# Sheet_motors.net
KiCad netlist of a schematic drawn in Altium Designer
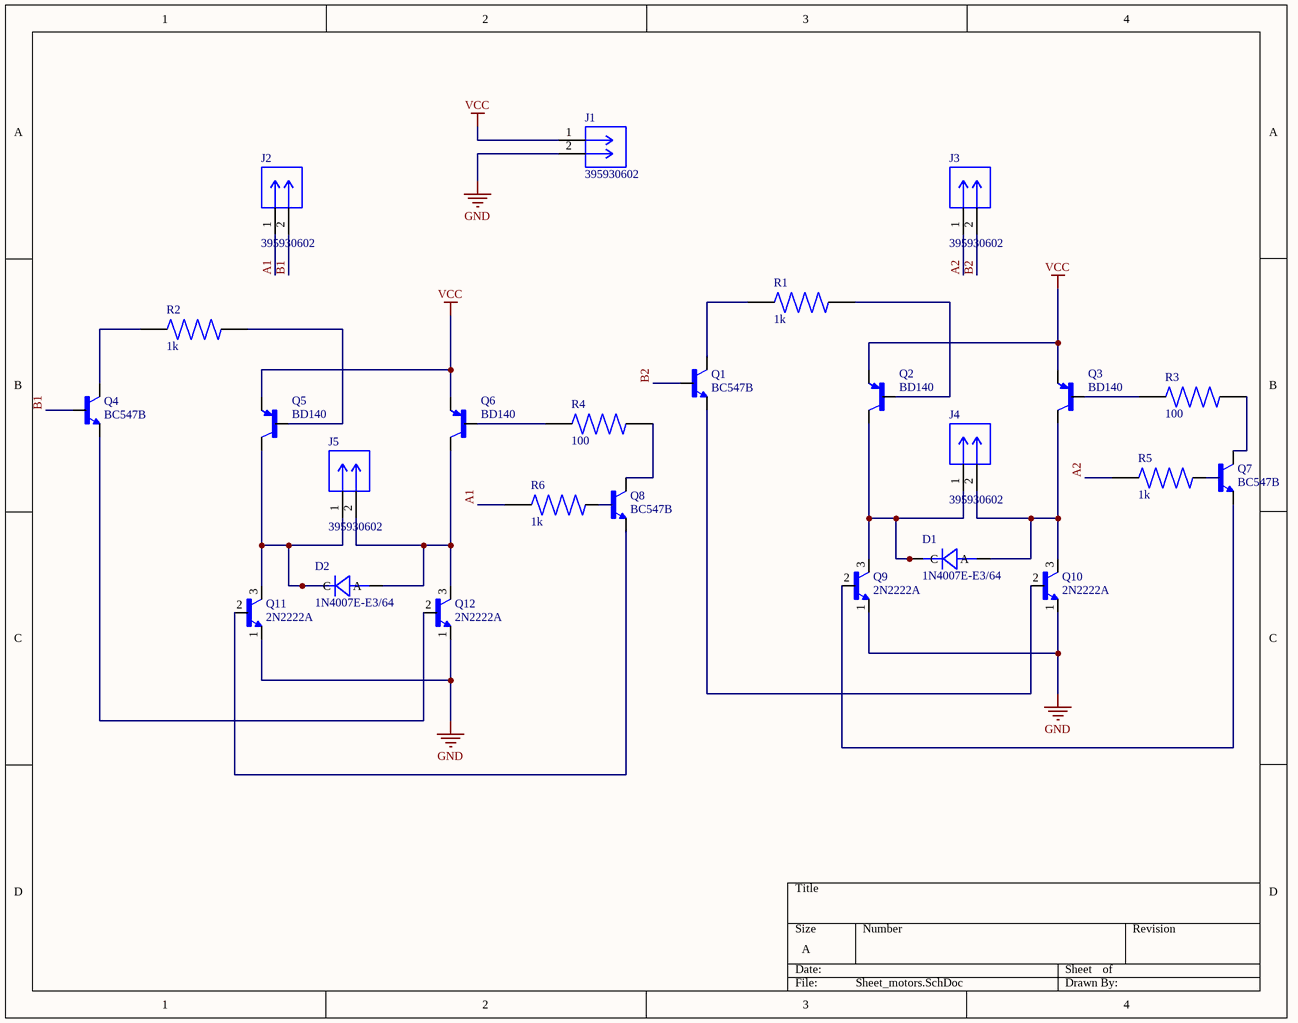
[diagram p0: Sheet_motors.SchDoc]

(export (version "E")
  (design (tool "Eeschema 10.0.6"))
  (components
    (comp (ref "D1")
      (value "1N4007E-E3/64")
      (footprint "DIOAD520W79L463D238")
      (description "Diode 1KV 1A 2-Pin DO-204AL T/R")
      (fields (field (name "MF") "Vishay Semiconductor"))
      (libsource (lib "1N4007E-E3_64") (part "1N4007E-E3/64"))
    )
    (comp (ref "D2")
      (value "1N4007E-E3/64")
      (footprint "DIOAD520W79L463D238")
      (description "Diode 1KV 1A 2-Pin DO-204AL T/R")
      (fields (field (name "MF") "Vishay Semiconductor"))
      (libsource (lib "1N4007E-E3_64") (part "1N4007E-E3/64"))
    )
    (comp (ref "J1")
      (value "395930602")
      (footprint "CONN_SD-39543-004_NONE_02P_MOL")
      (libsource (lib "395930602") (part "395930602"))
    )
    (comp (ref "J2")
      (value "395930602")
      (footprint "CONN_SD-39543-004_NONE_02P_MOL")
      (libsource (lib "395930602") (part "395930602"))
    )
    (comp (ref "J3")
      (value "395930602")
      (footprint "CONN_SD-39543-004_NONE_02P_MOL")
      (libsource (lib "395930602") (part "395930602"))
    )
    (comp (ref "J4")
      (value "395930602")
      (footprint "CONN_SD-39543-004_NONE_02P_MOL")
      (libsource (lib "395930602") (part "395930602"))
    )
    (comp (ref "J5")
      (value "395930602")
      (footprint "CONN_SD-39543-004_NONE_02P_MOL")
      (libsource (lib "395930602") (part "395930602"))
    )
    (comp (ref "Q1")
      (value "BC547B")
      (footprint "TO92250P510H770-3")
      (description "Bipolar (BJT) TransistÃ¶r NPN 45 V 100 mA 300MHz 625 mW Delikten TO-92 (TO-226)")
      (fields (field (name "MF") "ON Semiconductor"))
      (libsource (lib "BC547B") (part "BC547B"))
    )
    (comp (ref "Q2")
      (value "BD140")
      (footprint "TO229P760X270X1364-3")
      (description "Bipolar (BJT) Transistor PNP 80 V 1.5 A - 1.25 W Through Hole TO-126-3")
      (fields (field (name "MF") "ON Semiconductor"))
      (libsource (lib "BD140") (part "BD140"))
    )
    (comp (ref "Q3")
      (value "BD140")
      (footprint "TO229P760X270X1364-3")
      (description "Bipolar (BJT) Transistor PNP 80 V 1.5 A - 1.25 W Through Hole TO-126-3")
      (fields (field (name "MF") "ON Semiconductor"))
      (libsource (lib "BD140") (part "BD140"))
    )
    (comp (ref "Q4")
      (value "BC547B")
      (footprint "TO92250P510H770-3")
      (description "Bipolar (BJT) TransistÃ¶r NPN 45 V 100 mA 300MHz 625 mW Delikten TO-92 (TO-226)")
      (fields (field (name "MF") "ON Semiconductor"))
      (libsource (lib "BC547B") (part "BC547B"))
    )
    (comp (ref "Q5")
      (value "BD140")
      (footprint "TO229P760X270X1364-3")
      (description "Bipolar (BJT) Transistor PNP 80 V 1.5 A - 1.25 W Through Hole TO-126-3")
      (fields (field (name "MF") "ON Semiconductor"))
      (libsource (lib "BD140") (part "BD140"))
    )
    (comp (ref "Q6")
      (value "BD140")
      (footprint "TO229P760X270X1364-3")
      (description "Bipolar (BJT) Transistor PNP 80 V 1.5 A - 1.25 W Through Hole TO-126-3")
      (fields (field (name "MF") "ON Semiconductor"))
      (libsource (lib "BD140") (part "BD140"))
    )
    (comp (ref "Q7")
      (value "BC547B")
      (footprint "TO92250P510H770-3")
      (description "Bipolar (BJT) TransistÃ¶r NPN 45 V 100 mA 300MHz 625 mW Delikten TO-92 (TO-226)")
      (fields (field (name "MF") "ON Semiconductor"))
      (libsource (lib "BC547B") (part "BC547B"))
    )
    (comp (ref "Q8")
      (value "BC547B")
      (footprint "TO92250P510H770-3")
      (description "Bipolar (BJT) TransistÃ¶r NPN 45 V 100 mA 300MHz 625 mW Delikten TO-92 (TO-226)")
      (fields (field (name "MF") "ON Semiconductor"))
      (libsource (lib "BC547B") (part "BC547B"))
    )
    (comp (ref "Q9")
      (value "2N2222A")
      (footprint "TO127P584H533-3")
      (description "Bipolar (BJT) Transistor NPN 50 V 800 mA - 500 mW Surface Mount 4-SMD")
      (fields (field (name "MF") "Microsemi Corporation"))
      (libsource (lib "2N2222A (1)") (part "2N2222A"))
    )
    (comp (ref "Q10")
      (value "2N2222A")
      (footprint "TO127P584H533-3")
      (description "Bipolar (BJT) Transistor NPN 50 V 800 mA - 500 mW Surface Mount 4-SMD")
      (fields (field (name "MF") "Microsemi Corporation"))
      (libsource (lib "2N2222A (1)") (part "2N2222A"))
    )
    (comp (ref "Q11")
      (value "2N2222A")
      (footprint "TO127P584H533-3")
      (description "Bipolar (BJT) Transistor NPN 50 V 800 mA - 500 mW Surface Mount 4-SMD")
      (fields (field (name "MF") "Microsemi Corporation"))
      (libsource (lib "2N2222A (1)") (part "2N2222A"))
    )
    (comp (ref "Q12")
      (value "2N2222A")
      (footprint "TO127P584H533-3")
      (description "Bipolar (BJT) Transistor NPN 50 V 800 mA - 500 mW Surface Mount 4-SMD")
      (fields (field (name "MF") "Microsemi Corporation"))
      (libsource (lib "2N2222A (1)") (part "2N2222A"))
    )
    (comp (ref "R1")
      (value "1k")
      (footprint "RESAD1100W55L680D260")
      (description "100 kOhms Â±1% 0.25W, 1/4W Through Hole Resistor Axial - Metal Film")
      (fields (field (name "MF") "Yageo") (field (name "MP") "MFR-25FBF52-100K"))
      (libsource (lib "MFR-25FBF52-100K") (part "MFR-25FBF52-100K"))
    )
    (comp (ref "R2")
      (value "1k")
      (footprint "RESAD1100W55L680D260")
      (description "100 kOhms Â±1% 0.25W, 1/4W Through Hole Resistor Axial - Metal Film")
      (fields (field (name "MF") "Yageo") (field (name "MP") "MFR-25FBF52-100K"))
      (libsource (lib "MFR-25FBF52-100K") (part "MFR-25FBF52-100K"))
    )
    (comp (ref "R3")
      (value "100")
      (footprint "RESAD1100W55L680D260")
      (description "100 kOhms Â±1% 0.25W, 1/4W Through Hole Resistor Axial - Metal Film")
      (fields (field (name "MF") "Yageo") (field (name "MP") "MFR-25FBF52-100K"))
      (libsource (lib "MFR-25FBF52-100K") (part "MFR-25FBF52-100K"))
    )
    (comp (ref "R4")
      (value "100")
      (footprint "RESAD1100W55L680D260")
      (description "100 kOhms Â±1% 0.25W, 1/4W Through Hole Resistor Axial - Metal Film")
      (fields (field (name "MF") "Yageo") (field (name "MP") "MFR-25FBF52-100K"))
      (libsource (lib "MFR-25FBF52-100K") (part "MFR-25FBF52-100K"))
    )
    (comp (ref "R5")
      (value "1k")
      (footprint "RESAD1100W55L680D260")
      (description "100 kOhms Â±1% 0.25W, 1/4W Through Hole Resistor Axial - Metal Film")
      (fields (field (name "MF") "Yageo") (field (name "MP") "MFR-25FBF52-100K"))
      (libsource (lib "MFR-25FBF52-100K") (part "MFR-25FBF52-100K"))
    )
    (comp (ref "R6")
      (value "1k")
      (footprint "RESAD1100W55L680D260")
      (description "100 kOhms Â±1% 0.25W, 1/4W Through Hole Resistor Axial - Metal Film")
      (fields (field (name "MF") "Yageo") (field (name "MP") "MFR-25FBF52-100K"))
      (libsource (lib "MFR-25FBF52-100K") (part "MFR-25FBF52-100K"))
    )
  )
  (nets
    (net (code "1") (name "/A1") (class "Default")
      (node (ref "J2") (pin "1") (pinfunction "1_1") (pintype "passive"))
      (node (ref "R6") (pin "1") (pinfunction "1_1") (pintype "passive"))
    )
    (net (code "2") (name "/A2") (class "Default")
      (node (ref "J3") (pin "1") (pinfunction "1_1") (pintype "passive"))
      (node (ref "R5") (pin "1") (pinfunction "1_1") (pintype "passive"))
    )
    (net (code "3") (name "/B1") (class "Default")
      (node (ref "J2") (pin "2") (pinfunction "2_2") (pintype "passive"))
      (node (ref "Q4") (pin "2") (pinfunction "B_2") (pintype "passive"))
    )
    (net (code "4") (name "/B2") (class "Default")
      (node (ref "J3") (pin "2") (pinfunction "2_2") (pintype "passive"))
      (node (ref "Q1") (pin "2") (pinfunction "B_2") (pintype "passive"))
    )
    (net (code "5") (name "GND") (class "Default")
      (node (ref "J1") (pin "2") (pinfunction "2_2") (pintype "passive"))
      (node (ref "Q10") (pin "1") (pinfunction "E_1") (pintype "passive"))
      (node (ref "Q11") (pin "1") (pinfunction "E_1") (pintype "passive"))
      (node (ref "Q12") (pin "1") (pinfunction "E_1") (pintype "passive"))
      (node (ref "Q9") (pin "1") (pinfunction "E_1") (pintype "passive"))
    )
    (net (code "6") (name "Net-(Q1-C)") (class "Default")
      (node (ref "Q1") (pin "1") (pinfunction "C_1") (pintype "passive"))
      (node (ref "R1") (pin "1") (pinfunction "1_1") (pintype "passive"))
    )
    (net (code "7") (name "Net-(Q1-E)") (class "Default")
      (node (ref "Q1") (pin "3") (pinfunction "E_3") (pintype "passive"))
      (node (ref "Q10") (pin "2") (pinfunction "B_2") (pintype "passive"))
    )
    (net (code "8") (name "Net-(Q2-B)") (class "Default")
      (node (ref "Q2") (pin "3") (pinfunction "B_3") (pintype "passive"))
      (node (ref "R1") (pin "2") (pinfunction "2_2") (pintype "passive"))
    )
    (net (code "9") (name "Net-(Q2-C)") (class "Default")
      (node (ref "D1") (pin "C") (pinfunction "C_C") (pintype "passive"))
      (node (ref "J4") (pin "1") (pinfunction "1_1") (pintype "passive"))
      (node (ref "Q2") (pin "2") (pinfunction "C_2") (pintype "passive"))
      (node (ref "Q9") (pin "3") (pinfunction "C_3") (pintype "passive"))
    )
    (net (code "10") (name "Net-(Q3-B)") (class "Default")
      (node (ref "Q3") (pin "3") (pinfunction "B_3") (pintype "passive"))
      (node (ref "R3") (pin "1") (pinfunction "1_1") (pintype "passive"))
    )
    (net (code "11") (name "Net-(Q4-C)") (class "Default")
      (node (ref "Q4") (pin "1") (pinfunction "C_1") (pintype "passive"))
      (node (ref "R2") (pin "1") (pinfunction "1_1") (pintype "passive"))
    )
    (net (code "12") (name "Net-(Q5-B)") (class "Default")
      (node (ref "Q5") (pin "3") (pinfunction "B_3") (pintype "passive"))
      (node (ref "R2") (pin "2") (pinfunction "2_2") (pintype "passive"))
    )
    (net (code "13") (name "Net-(Q6-B)") (class "Default")
      (node (ref "Q6") (pin "3") (pinfunction "B_3") (pintype "passive"))
      (node (ref "R4") (pin "1") (pinfunction "1_1") (pintype "passive"))
    )
    (net (code "14") (name "Net-(Q7-B)") (class "Default")
      (node (ref "Q7") (pin "2") (pinfunction "B_2") (pintype "passive"))
      (node (ref "R5") (pin "2") (pinfunction "2_2") (pintype "passive"))
    )
    (net (code "15") (name "Net-(Q7-C)") (class "Default")
      (node (ref "Q7") (pin "1") (pinfunction "C_1") (pintype "passive"))
      (node (ref "R3") (pin "2") (pinfunction "2_2") (pintype "passive"))
    )
    (net (code "16") (name "Net-(Q7-E)") (class "Default")
      (node (ref "Q7") (pin "3") (pinfunction "E_3") (pintype "passive"))
      (node (ref "Q9") (pin "2") (pinfunction "B_2") (pintype "passive"))
    )
    (net (code "17") (name "Net-(Q8-B)") (class "Default")
      (node (ref "Q8") (pin "2") (pinfunction "B_2") (pintype "passive"))
      (node (ref "R6") (pin "2") (pinfunction "2_2") (pintype "passive"))
    )
    (net (code "18") (name "Net-(Q8-C)") (class "Default")
      (node (ref "Q8") (pin "1") (pinfunction "C_1") (pintype "passive"))
      (node (ref "R4") (pin "2") (pinfunction "2_2") (pintype "passive"))
    )
    (net (code "19") (name "Net-(Q10-C)") (class "Default")
      (node (ref "D1") (pin "A") (pinfunction "A_A") (pintype "passive"))
      (node (ref "J4") (pin "2") (pinfunction "2_2") (pintype "passive"))
      (node (ref "Q10") (pin "3") (pinfunction "C_3") (pintype "passive"))
      (node (ref "Q3") (pin "2") (pinfunction "C_2") (pintype "passive"))
    )
    (net (code "20") (name "Net-(Q11-B)") (class "Default")
      (node (ref "Q11") (pin "2") (pinfunction "B_2") (pintype "passive"))
      (node (ref "Q8") (pin "3") (pinfunction "E_3") (pintype "passive"))
    )
    (net (code "21") (name "Net-(Q11-C)") (class "Default")
      (node (ref "D2") (pin "C") (pinfunction "C_C") (pintype "passive"))
      (node (ref "J5") (pin "1") (pinfunction "1_1") (pintype "passive"))
      (node (ref "Q11") (pin "3") (pinfunction "C_3") (pintype "passive"))
      (node (ref "Q5") (pin "2") (pinfunction "C_2") (pintype "passive"))
    )
    (net (code "22") (name "Net-(Q12-B)") (class "Default")
      (node (ref "Q12") (pin "2") (pinfunction "B_2") (pintype "passive"))
      (node (ref "Q4") (pin "3") (pinfunction "E_3") (pintype "passive"))
    )
    (net (code "23") (name "Net-(Q12-C)") (class "Default")
      (node (ref "D2") (pin "A") (pinfunction "A_A") (pintype "passive"))
      (node (ref "J5") (pin "2") (pinfunction "2_2") (pintype "passive"))
      (node (ref "Q12") (pin "3") (pinfunction "C_3") (pintype "passive"))
      (node (ref "Q6") (pin "2") (pinfunction "C_2") (pintype "passive"))
    )
    (net (code "24") (name "VCC") (class "Default")
      (node (ref "J1") (pin "1") (pinfunction "1_1") (pintype "passive"))
      (node (ref "Q2") (pin "1") (pinfunction "E_1") (pintype "passive"))
      (node (ref "Q3") (pin "1") (pinfunction "E_1") (pintype "passive"))
      (node (ref "Q5") (pin "1") (pinfunction "E_1") (pintype "passive"))
      (node (ref "Q6") (pin "1") (pinfunction "E_1") (pintype "passive"))
    )
  )
)
